# EasyEDA_PCB_VTimer_button.net
KiCad netlist of a schematic drawn in EasyEDA
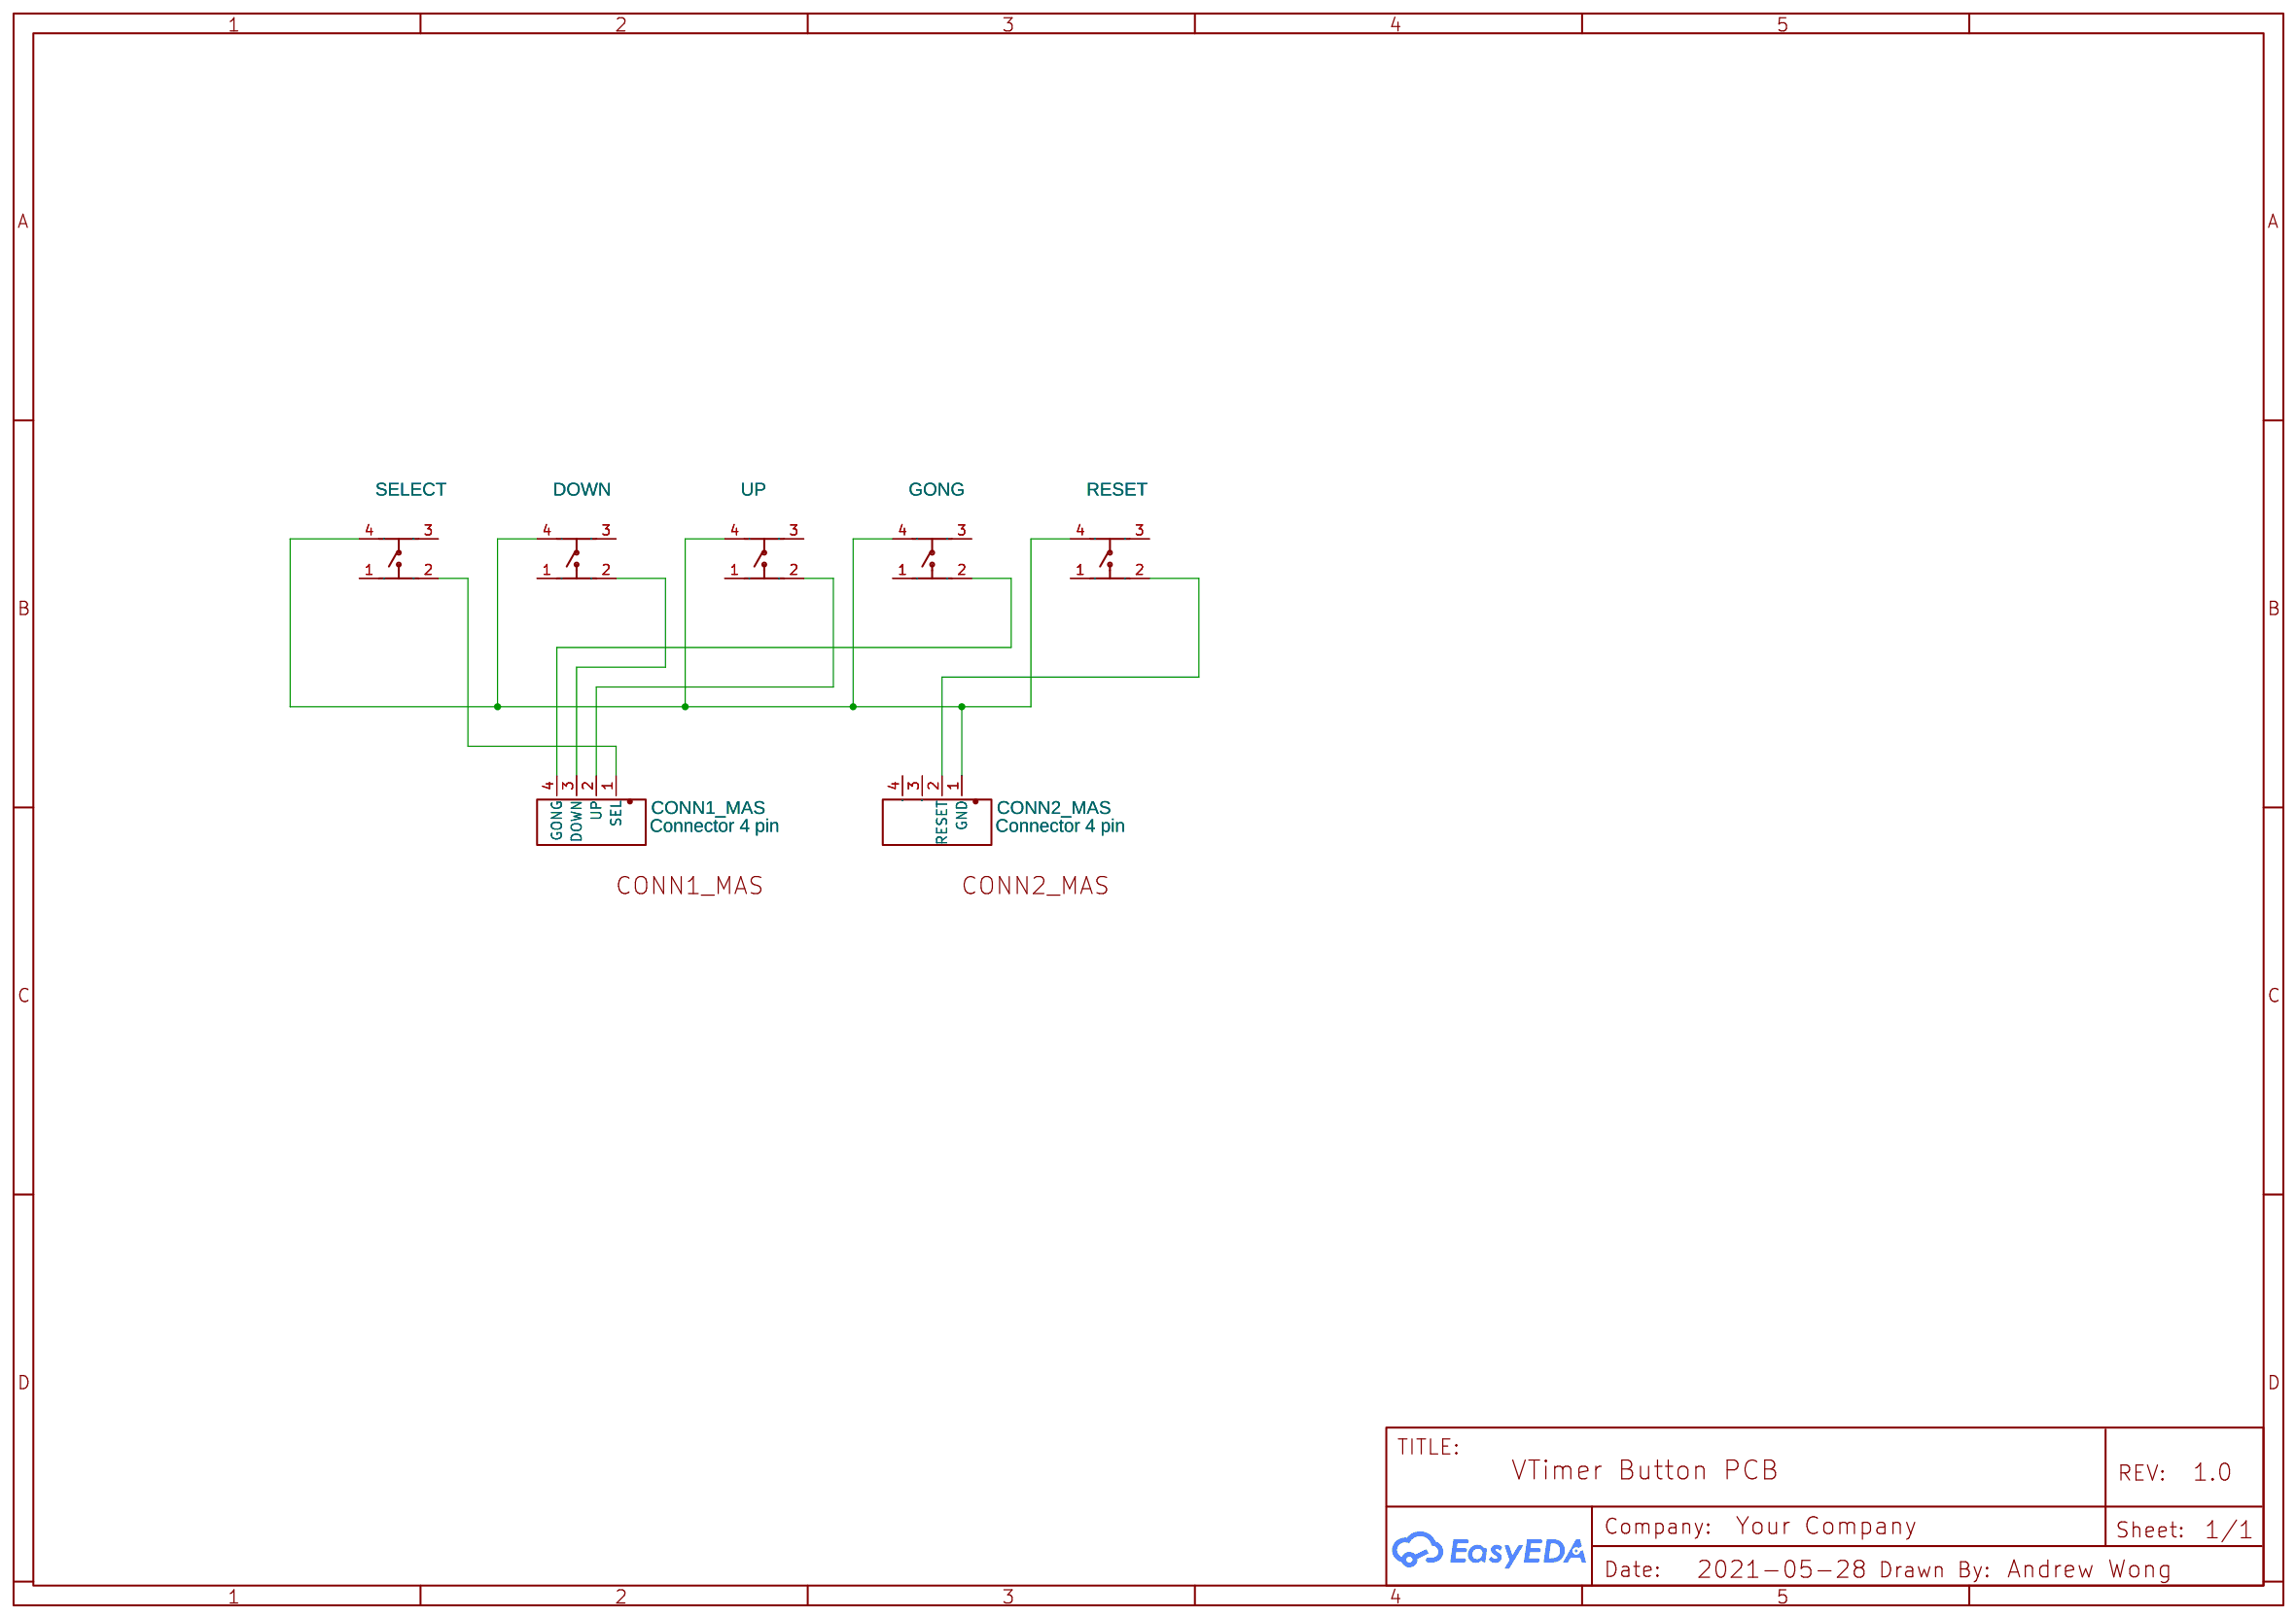
[diagram p0: schematic sheet]

(export (version "E")
  (design (tool "Eeschema 10.0.6"))
  (components
    (comp (ref "CONN1_MAS")
      (value "Connector 4 pin")
      (fields
        (field (name "BOM_Manufacturer Part") "Connector KF2510-8A")
        (field (name "BOM_Supplier Part") "C27837")
      )
      (libsource (lib "") (part "Connector 4 pin"))
    )
    (comp (ref "CONN2_MAS")
      (value "Connector 4 pin")
      (fields
        (field (name "BOM_Manufacturer Part") "Connector KF2510-8A")
        (field (name "BOM_Supplier Part") "C27837")
      )
      (libsource (lib "") (part "Connector 4 pin_1"))
    )
    (comp (ref "DOWN")
      (value "DOWN")
      (fields
        (field (name "BOM_Manufacturer Part") "TL1100DF160Q")
        (field (name "BOM_Supplier Part") "C273460")
      )
      (libsource (lib "") (part "TL1100DF160Q_3"))
    )
    (comp (ref "GONG")
      (value "GONG")
      (fields
        (field (name "BOM_Manufacturer Part") "TL1100DF160Q")
        (field (name "BOM_Supplier Part") "C273460")
      )
      (libsource (lib "") (part "TL1100DF160Q_2"))
    )
    (comp (ref "RESET")
      (value "RESET")
      (fields
        (field (name "BOM_Manufacturer Part") "TL1100DF160Q")
        (field (name "BOM_Supplier Part") "C273460")
      )
      (libsource (lib "") (part "TL1100DF160Q_4"))
    )
    (comp (ref "SELECT")
      (value "SELECT")
      (fields
        (field (name "BOM_Manufacturer Part") "TL1100DF160Q")
        (field (name "BOM_Supplier Part") "C273460")
      )
      (libsource (lib "") (part "TL1100DF160Q"))
    )
    (comp (ref "UP")
      (value "UP")
      (fields
        (field (name "BOM_Manufacturer Part") "TL1100DF160Q")
        (field (name "BOM_Supplier Part") "C273460")
      )
      (libsource (lib "") (part "TL1100DF160Q_1"))
    )
  )
  (nets
    (net (code "1") (name "Net-(CONN1_MAS-DOWN)") (class "Default")
      (node (ref "CONN1_MAS") (pin "3") (pinfunction "DOWN_3") (pintype "unspecified"))
      (node (ref "DOWN") (pin "2") (pinfunction "2_2") (pintype "unspecified"))
    )
    (net (code "2") (name "Net-(CONN1_MAS-GONG)") (class "Default")
      (node (ref "CONN1_MAS") (pin "4") (pinfunction "GONG_4") (pintype "unspecified"))
      (node (ref "GONG") (pin "2") (pinfunction "2_2") (pintype "unspecified"))
    )
    (net (code "3") (name "Net-(CONN1_MAS-SEL)") (class "Default")
      (node (ref "CONN1_MAS") (pin "1") (pinfunction "SEL_1") (pintype "unspecified"))
      (node (ref "SELECT") (pin "2") (pinfunction "2_2") (pintype "unspecified"))
    )
    (net (code "4") (name "Net-(CONN1_MAS-UP)") (class "Default")
      (node (ref "CONN1_MAS") (pin "2") (pinfunction "UP_2") (pintype "unspecified"))
      (node (ref "UP") (pin "2") (pinfunction "2_2") (pintype "unspecified"))
    )
    (net (code "5") (name "Net-(CONN2_MAS-GND)") (class "Default")
      (node (ref "CONN2_MAS") (pin "1") (pinfunction "GND_1") (pintype "unspecified"))
      (node (ref "DOWN") (pin "4") (pinfunction "4_4") (pintype "unspecified"))
      (node (ref "GONG") (pin "4") (pinfunction "4_4") (pintype "unspecified"))
      (node (ref "RESET") (pin "4") (pinfunction "4_4") (pintype "unspecified"))
      (node (ref "SELECT") (pin "4") (pinfunction "4_4") (pintype "unspecified"))
      (node (ref "UP") (pin "4") (pinfunction "4_4") (pintype "unspecified"))
    )
    (net (code "6") (name "Net-(CONN2_MAS-RESET)") (class "Default")
      (node (ref "CONN2_MAS") (pin "2") (pinfunction "RESET_2") (pintype "unspecified"))
      (node (ref "RESET") (pin "2") (pinfunction "2_2") (pintype "unspecified"))
    )
    (net (code "7") (name "unconnected-(CONN2_MAS-Pad3)") (class "Default")
      (node (ref "CONN2_MAS") (pin "3") (pinfunction "3_3") (pintype "unspecified"))
    )
    (net (code "8") (name "unconnected-(CONN2_MAS-Pad4)") (class "Default")
      (node (ref "CONN2_MAS") (pin "4") (pinfunction "4_4") (pintype "unspecified"))
    )
    (net (code "9") (name "unconnected-(DOWN-Pad1)") (class "Default")
      (node (ref "DOWN") (pin "1") (pinfunction "1_1") (pintype "unspecified"))
    )
    (net (code "10") (name "unconnected-(DOWN-Pad3)") (class "Default")
      (node (ref "DOWN") (pin "3") (pinfunction "3_3") (pintype "unspecified"))
    )
    (net (code "11") (name "unconnected-(GONG-Pad1)") (class "Default")
      (node (ref "GONG") (pin "1") (pinfunction "1_1") (pintype "unspecified"))
    )
    (net (code "12") (name "unconnected-(GONG-Pad3)") (class "Default")
      (node (ref "GONG") (pin "3") (pinfunction "3_3") (pintype "unspecified"))
    )
    (net (code "13") (name "unconnected-(RESET-Pad1)") (class "Default")
      (node (ref "RESET") (pin "1") (pinfunction "1_1") (pintype "unspecified"))
    )
    (net (code "14") (name "unconnected-(RESET-Pad3)") (class "Default")
      (node (ref "RESET") (pin "3") (pinfunction "3_3") (pintype "unspecified"))
    )
    (net (code "15") (name "unconnected-(SELECT-Pad1)") (class "Default")
      (node (ref "SELECT") (pin "1") (pinfunction "1_1") (pintype "unspecified"))
    )
    (net (code "16") (name "unconnected-(SELECT-Pad3)") (class "Default")
      (node (ref "SELECT") (pin "3") (pinfunction "3_3") (pintype "unspecified"))
    )
    (net (code "17") (name "unconnected-(UP-Pad1)") (class "Default")
      (node (ref "UP") (pin "1") (pinfunction "1_1") (pintype "unspecified"))
    )
    (net (code "18") (name "unconnected-(UP-Pad3)") (class "Default")
      (node (ref "UP") (pin "3") (pinfunction "3_3") (pintype "unspecified"))
    )
  )
)
